# current_signal_adaptation.net
KiCad netlist of a schematic drawn in Altium Designer
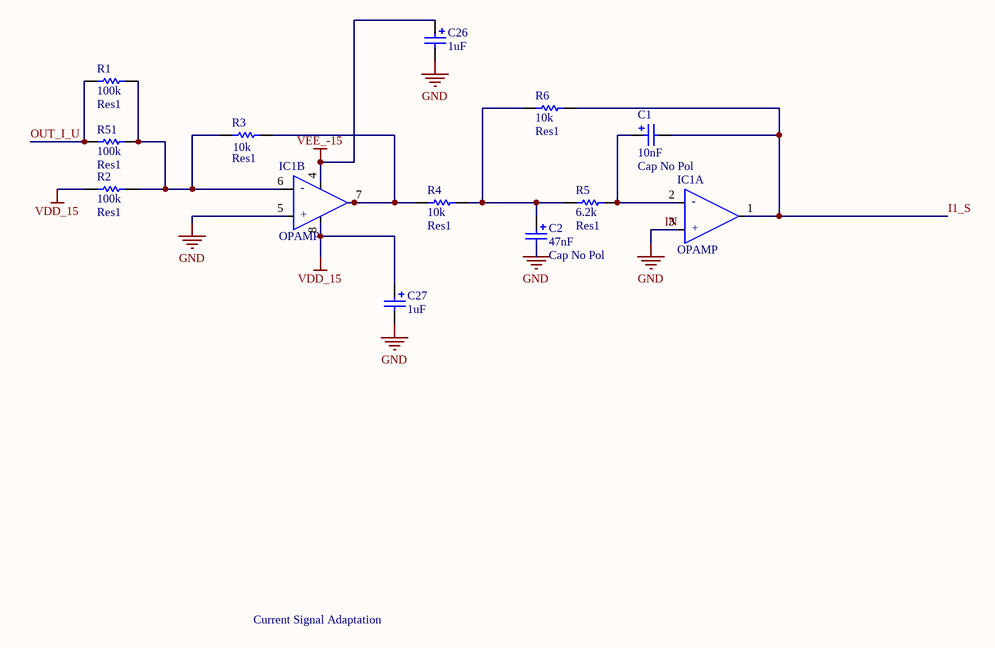
[diagram p0: current_signal_adaptation.SchDoc]

(export (version "E")
  (design (tool "Eeschema 10.0.6"))
  (components
    (comp (ref "C1")
      (value "Cap No Pol")
      (footprint "RAD-0.1")
      (description "Polarized Capacitor (Radial)")
      (fields (field (name "ALTIUM_VALUE") "10nF") (field (name "PUBLISHER") "Altium Limited"))
      (libsource (lib "LABSTEPS_Project") (part "Cap No Pol"))
    )
    (comp (ref "C2")
      (value "Cap No Pol")
      (footprint "RAD-0.1")
      (description "Polarized Capacitor (Radial)")
      (fields (field (name "ALTIUM_VALUE") "47nF") (field (name "PUBLISHER") "Altium Limited"))
      (libsource (lib "LABSTEPS_Project") (part "Cap No Pol"))
    )
    (comp (ref "C26")
      (value "1uF")
      (footprint "RAD-0.1")
      (description "Polarized Capacitor (Radial)")
      (fields (field (name "Comment") "Cap No Pol") (field (name "PUBLISHER") "Altium Limited"))
      (libsource (lib "LABSTEPS_Project") (part "Cap No Pol"))
    )
    (comp (ref "C27")
      (value "1uF")
      (footprint "RAD-0.1")
      (description "Polarized Capacitor (Radial)")
      (fields (field (name "Comment") "Cap No Pol") (field (name "PUBLISHER") "Altium Limited"))
      (libsource (lib "LABSTEPS_Project") (part "Cap No Pol"))
    )
    (comp (ref "IC1")
      (value "OPAMP")
      (footprint "DIP-8")
      (description "ADTL082")
      (libsource (lib "LABSTEPS_Project") (part "ADTL082"))
    )
    (comp (ref "R1")
      (value "Res1")
      (footprint "AXIAL-0.4")
      (description "Resistor")
      (fields (field (name "ALTIUM_VALUE") "100k") (field (name "PUBLISHER") "Altium Limited"))
      (libsource (lib "LABSTEPS_Project") (part "Res1"))
    )
    (comp (ref "R2")
      (value "Res1")
      (footprint "AXIAL-0.4")
      (description "Resistor")
      (fields (field (name "ALTIUM_VALUE") "100k") (field (name "PUBLISHER") "Altium Limited"))
      (libsource (lib "LABSTEPS_Project") (part "Res1"))
    )
    (comp (ref "R3")
      (value "Res1")
      (footprint "AXIAL-0.4")
      (description "Resistor")
      (fields (field (name "ALTIUM_VALUE") "10k") (field (name "PUBLISHER") "Altium Limited"))
      (libsource (lib "LABSTEPS_Project") (part "Res1"))
    )
    (comp (ref "R4")
      (value "Res1")
      (footprint "AXIAL-0.4")
      (description "Resistor")
      (fields (field (name "ALTIUM_VALUE") "10k") (field (name "PUBLISHER") "Altium Limited"))
      (libsource (lib "LABSTEPS_Project") (part "Res1"))
    )
    (comp (ref "R5")
      (value "Res1")
      (footprint "AXIAL-0.4")
      (description "Resistor")
      (fields (field (name "ALTIUM_VALUE") "6.2k") (field (name "PUBLISHER") "Altium Limited"))
      (libsource (lib "LABSTEPS_Project") (part "Res1"))
    )
    (comp (ref "R6")
      (value "Res1")
      (footprint "AXIAL-0.4")
      (description "Resistor")
      (fields (field (name "ALTIUM_VALUE") "10k") (field (name "PUBLISHER") "Altium Limited"))
      (libsource (lib "LABSTEPS_Project") (part "Res1"))
    )
    (comp (ref "R51")
      (value "Res1")
      (footprint "AXIAL-0.4")
      (description "Resistor")
      (fields (field (name "ALTIUM_VALUE") "100k") (field (name "PUBLISHER") "Altium Limited"))
      (libsource (lib "LABSTEPS_Project") (part "Res1"))
    )
  )
  (nets
    (net (code "1") (name "/I1_S") (class "Default")
      (node (ref "C1") (pin "2") (pinfunction "2_2") (pintype "passive"))
      (node (ref "IC1") (pin "1") (pinfunction "OUT_A_1") (pintype "passive"))
      (node (ref "R6") (pin "2") (pinfunction "2_2") (pintype "passive"))
    )
    (net (code "2") (name "/OUT_I_U") (class "Default")
      (node (ref "R1") (pin "1") (pinfunction "1_1") (pintype "passive"))
      (node (ref "R51") (pin "1") (pinfunction "1_1") (pintype "passive"))
    )
    (net (code "3") (name "GND") (class "Default")
      (node (ref "C2") (pin "2") (pinfunction "2_2") (pintype "passive"))
      (node (ref "C26") (pin "2") (pinfunction "2_2") (pintype "passive"))
      (node (ref "C27") (pin "2") (pinfunction "2_2") (pintype "passive"))
      (node (ref "IC1") (pin "3") (pinfunction "IN_A_+_3") (pintype "passive"))
      (node (ref "IC1") (pin "5") (pinfunction "IN_B_+_5") (pintype "passive"))
    )
    (net (code "4") (name "Net-(C2-Pad1)") (class "Default")
      (node (ref "C2") (pin "1") (pinfunction "1_1") (pintype "passive"))
      (node (ref "R4") (pin "2") (pinfunction "2_2") (pintype "passive"))
      (node (ref "R5") (pin "1") (pinfunction "1_1") (pintype "passive"))
      (node (ref "R6") (pin "1") (pinfunction "1_1") (pintype "passive"))
    )
    (net (code "5") (name "Net-(IC1A-IN_A_-)") (class "Default")
      (node (ref "C1") (pin "1") (pinfunction "1_1") (pintype "passive"))
      (node (ref "IC1") (pin "2") (pinfunction "IN_A_-_2") (pintype "passive"))
      (node (ref "R5") (pin "2") (pinfunction "2_2") (pintype "passive"))
    )
    (net (code "6") (name "Net-(IC1B-OUT_B)") (class "Default")
      (node (ref "IC1") (pin "7") (pinfunction "OUT_B_7") (pintype "passive"))
      (node (ref "R3") (pin "2") (pinfunction "2_2") (pintype "passive"))
      (node (ref "R4") (pin "1") (pinfunction "1_1") (pintype "passive"))
    )
    (net (code "7") (name "Net-(R1-Pad2)") (class "Default")
      (node (ref "R1") (pin "2") (pinfunction "2_2") (pintype "passive"))
      (node (ref "R2") (pin "2") (pinfunction "2_2") (pintype "passive"))
      (node (ref "R3") (pin "1") (pinfunction "1_1") (pintype "passive"))
      (node (ref "R51") (pin "2") (pinfunction "2_2") (pintype "passive"))
    )
    (net (code "8") (name "VDD_15") (class "Default")
      (node (ref "C27") (pin "1") (pinfunction "1_1") (pintype "passive"))
      (node (ref "IC1") (pin "8") (pinfunction "V+_8") (pintype "passive"))
      (node (ref "R2") (pin "1") (pinfunction "1_1") (pintype "passive"))
    )
    (net (code "9") (name "VEE_-15") (class "Default")
      (node (ref "C26") (pin "1") (pinfunction "1_1") (pintype "passive"))
      (node (ref "IC1") (pin "4") (pinfunction "-V_4") (pintype "passive"))
    )
    (net (code "10") (name "unconnected-(IC1B-IN_B_--Pad6)") (class "Default")
      (node (ref "IC1") (pin "6") (pinfunction "IN_B_-_6") (pintype "passive"))
    )
  )
)
